# TRACKER.net
KiCad netlist of a schematic drawn in Altium Designer
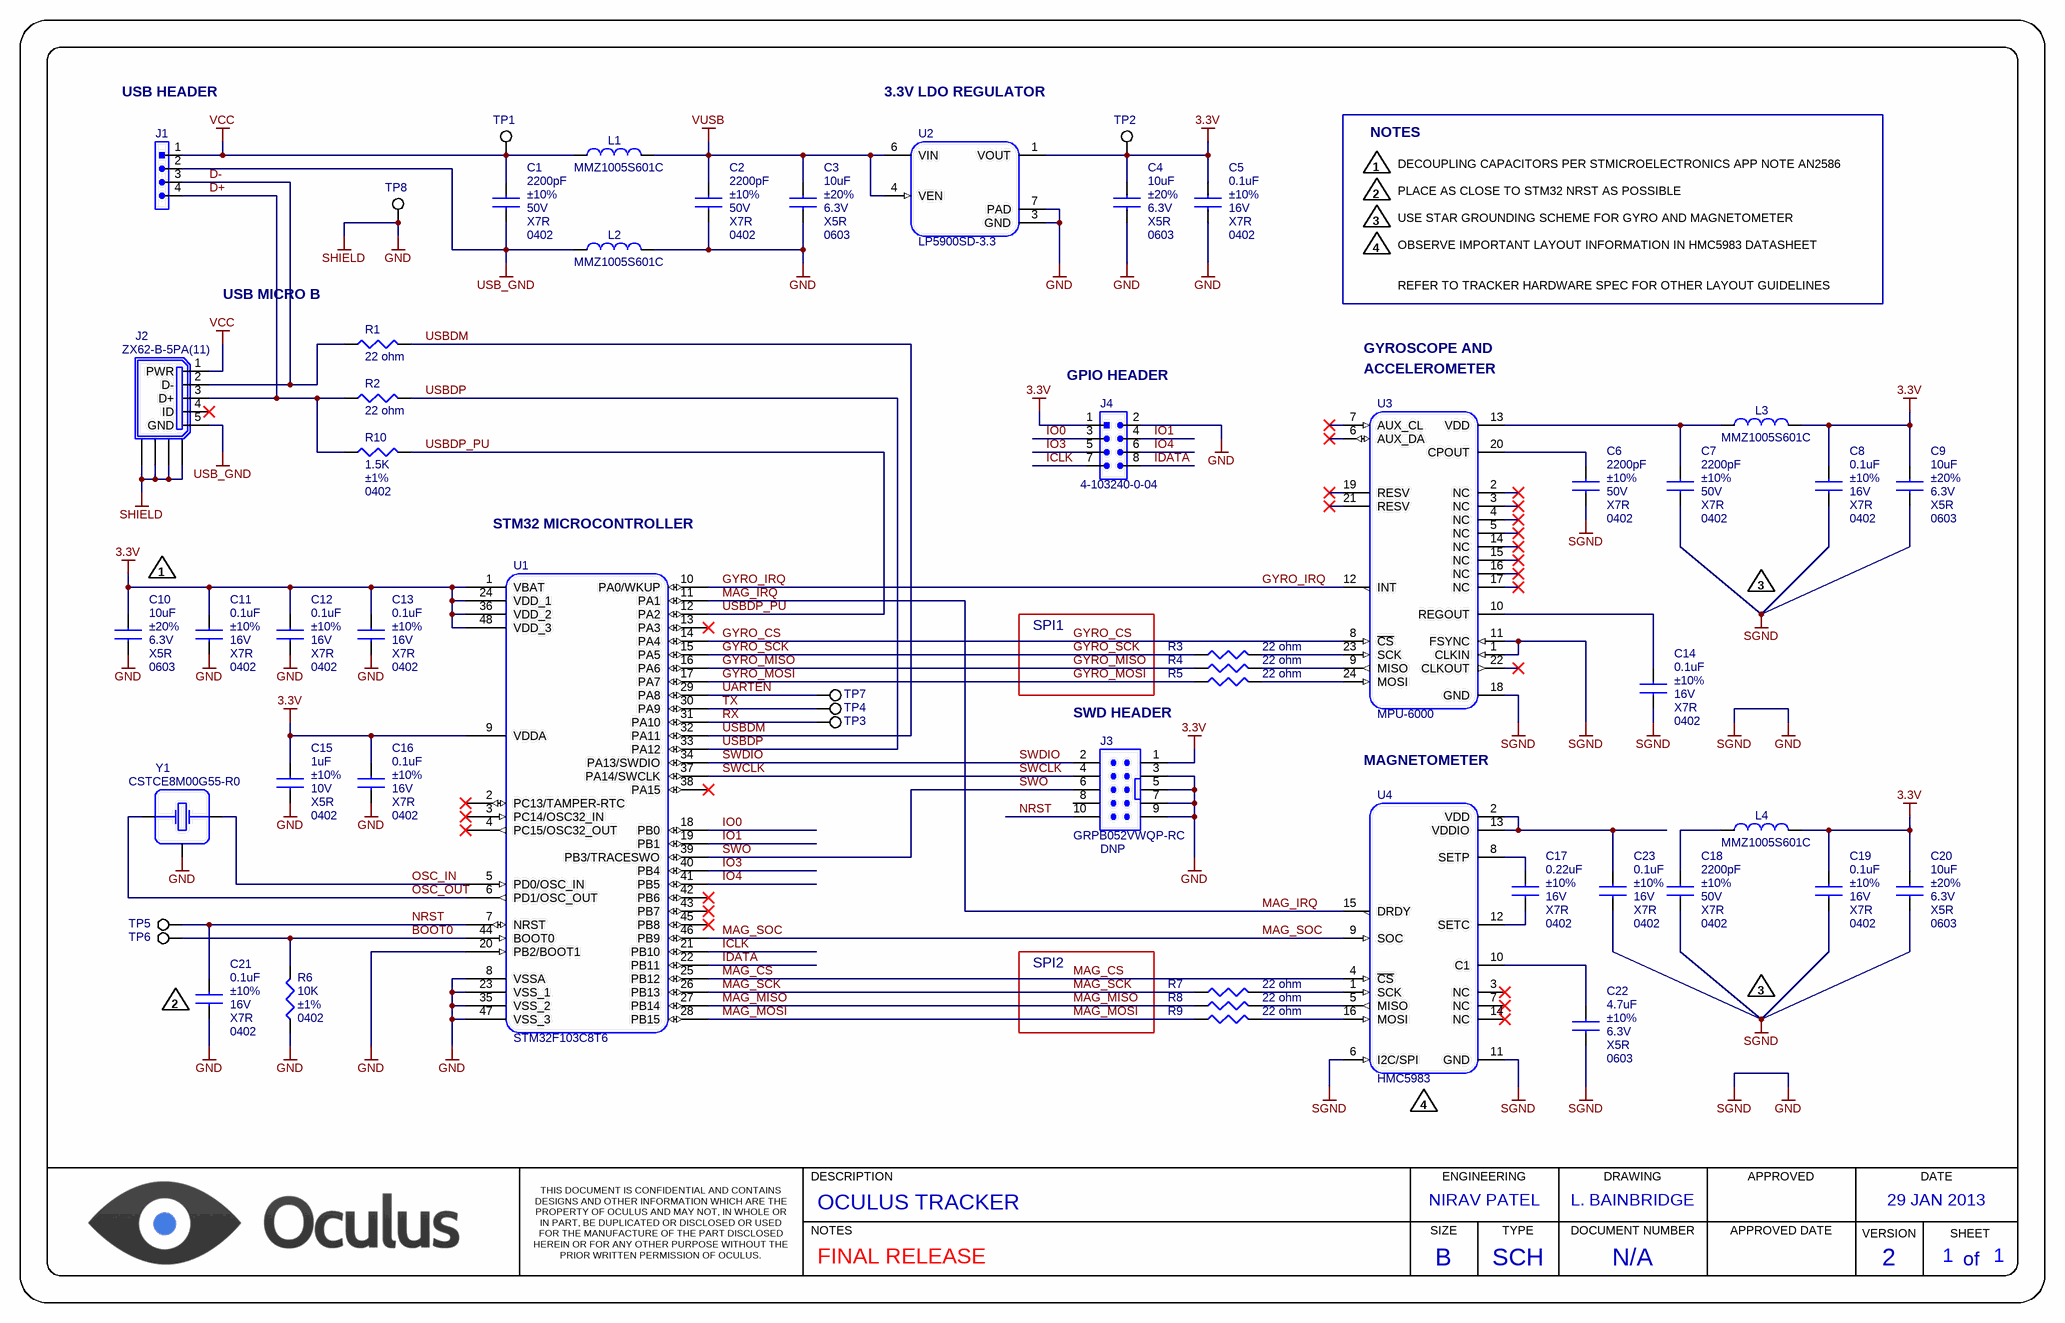
[diagram p0: TRACKER.SchDoc]

(export (version "E")
  (design (tool "Eeschema 10.0.6"))
  (components
    (comp (ref "C1")
      (value "2200pF")
      (footprint "CAP_CERAMIC_0402")
      (description "CAP, CERAMIC, 2200pF, ±10%, 50V, X7R, 0402")
      (fields
        (field (name "MANUFACTURER") "MURATA ELECTRONICS")
        (field (name "PART NUMBER") "GRM155R71H222KA01D")
        (field (name "TOLERANCE") "±10%")
        (field (name "VOLTAGE") "50V")
        (field (name "DIELECTRIC") "X7R")
        (field (name "PACKAGE") "0402")
      )
      (libsource (lib "TRACKER") (part "CAP, CERAMIC"))
    )
    (comp (ref "C2")
      (value "2200pF")
      (footprint "CAP_CERAMIC_0402")
      (description "CAP, CERAMIC, 2200pF, ±10%, 50V, X7R, 0402")
      (fields
        (field (name "MANUFACTURER") "MURATA ELECTRONICS")
        (field (name "PART NUMBER") "GRM155R71H222KA01D")
        (field (name "TOLERANCE") "±10%")
        (field (name "VOLTAGE") "50V")
        (field (name "DIELECTRIC") "X7R")
        (field (name "PACKAGE") "0402")
      )
      (libsource (lib "TRACKER") (part "CAP, CERAMIC"))
    )
    (comp (ref "C3")
      (value "10uF")
      (footprint "CAP_CERAMIC_0603")
      (description "CAP, CERAMIC, 10uF, ±20%, 6.3V, X5R, 0603")
      (fields
        (field (name "MANUFACTURER") "MURATA ELECTRONICS")
        (field (name "PART NUMBER") "GRM188R60J106ME47D")
        (field (name "TOLERANCE") "±20%")
        (field (name "VOLTAGE") "6.3V")
        (field (name "DIELECTRIC") "X5R")
        (field (name "PACKAGE") "0603")
      )
      (libsource (lib "TRACKER") (part "CAP, CERAMIC"))
    )
    (comp (ref "C4")
      (value "10uF")
      (footprint "CAP_CERAMIC_0603")
      (description "CAP, CERAMIC, 10uF, ±20%, 6.3V, X5R, 0603")
      (fields
        (field (name "MANUFACTURER") "MURATA ELECTRONICS")
        (field (name "PART NUMBER") "GRM188R60J106ME47D")
        (field (name "TOLERANCE") "±20%")
        (field (name "VOLTAGE") "6.3V")
        (field (name "DIELECTRIC") "X5R")
        (field (name "PACKAGE") "0603")
      )
      (libsource (lib "TRACKER") (part "CAP, CERAMIC"))
    )
    (comp (ref "C5")
      (value "0.1uF")
      (footprint "CAP_CERAMIC_0402")
      (description "CAP, CERAMIC, 0.1uF, ±10%, 16V, X7R, 0402")
      (fields
        (field (name "MANUFACTURER") "MURATA ELECTRONICS")
        (field (name "PART NUMBER") "GRM155R71C104KA88D")
        (field (name "TOLERANCE") "±10%")
        (field (name "VOLTAGE") "16V")
        (field (name "DIELECTRIC") "X7R")
        (field (name "PACKAGE") "0402")
      )
      (libsource (lib "TRACKER") (part "CAP, CERAMIC"))
    )
    (comp (ref "C6")
      (value "2200pF")
      (footprint "CAP_CERAMIC_0402")
      (description "CAP, CERAMIC, 2200pF, ±10%, 50V, X7R, 0402")
      (fields
        (field (name "MANUFACTURER") "MURATA ELECTRONICS")
        (field (name "PART NUMBER") "GRM155R71H222KA01D")
        (field (name "TOLERANCE") "±10%")
        (field (name "VOLTAGE") "50V")
        (field (name "DIELECTRIC") "X7R")
        (field (name "PACKAGE") "0402")
      )
      (libsource (lib "TRACKER") (part "CAP, CERAMIC"))
    )
    (comp (ref "C7")
      (value "2200pF")
      (footprint "CAP_CERAMIC_0402")
      (description "CAP, CERAMIC, 2200pF, ±10%, 50V, X7R, 0402")
      (fields
        (field (name "MANUFACTURER") "MURATA ELECTRONICS")
        (field (name "PART NUMBER") "GRM155R71H222KA01D")
        (field (name "TOLERANCE") "±10%")
        (field (name "VOLTAGE") "50V")
        (field (name "DIELECTRIC") "X7R")
        (field (name "PACKAGE") "0402")
      )
      (libsource (lib "TRACKER") (part "CAP, CERAMIC"))
    )
    (comp (ref "C8")
      (value "0.1uF")
      (footprint "CAP_CERAMIC_0402")
      (description "CAP, CERAMIC, 0.1uF, ±10%, 16V, X7R, 0402")
      (fields
        (field (name "MANUFACTURER") "MURATA ELECTRONICS")
        (field (name "PART NUMBER") "GRM155R71C104KA88D")
        (field (name "TOLERANCE") "±10%")
        (field (name "VOLTAGE") "16V")
        (field (name "DIELECTRIC") "X7R")
        (field (name "PACKAGE") "0402")
      )
      (libsource (lib "TRACKER") (part "CAP, CERAMIC"))
    )
    (comp (ref "C9")
      (value "10uF")
      (footprint "CAP_CERAMIC_0603")
      (description "CAP, CERAMIC, 10uF, ±20%, 6.3V, X5R, 0603")
      (fields
        (field (name "MANUFACTURER") "MURATA ELECTRONICS")
        (field (name "PART NUMBER") "GRM188R60J106ME47D")
        (field (name "TOLERANCE") "±20%")
        (field (name "VOLTAGE") "6.3V")
        (field (name "DIELECTRIC") "X5R")
        (field (name "PACKAGE") "0603")
      )
      (libsource (lib "TRACKER") (part "CAP, CERAMIC"))
    )
    (comp (ref "C10")
      (value "10uF")
      (footprint "CAP_CERAMIC_0603")
      (description "CAP, CERAMIC, 10uF, ±20%, 6.3V, X5R, 0603")
      (fields
        (field (name "MANUFACTURER") "MURATA ELECTRONICS")
        (field (name "PART NUMBER") "GRM188R60J106ME47D")
        (field (name "TOLERANCE") "±20%")
        (field (name "VOLTAGE") "6.3V")
        (field (name "DIELECTRIC") "X5R")
        (field (name "PACKAGE") "0603")
      )
      (libsource (lib "TRACKER") (part "CAP, CERAMIC"))
    )
    (comp (ref "C11")
      (value "0.1uF")
      (footprint "CAP_CERAMIC_0402")
      (description "CAP, CERAMIC, 0.1uF, ±10%, 16V, X7R, 0402")
      (fields
        (field (name "MANUFACTURER") "MURATA ELECTRONICS")
        (field (name "PART NUMBER") "GRM155R71C104KA88D")
        (field (name "TOLERANCE") "±10%")
        (field (name "VOLTAGE") "16V")
        (field (name "DIELECTRIC") "X7R")
        (field (name "PACKAGE") "0402")
      )
      (libsource (lib "TRACKER") (part "CAP, CERAMIC"))
    )
    (comp (ref "C12")
      (value "0.1uF")
      (footprint "CAP_CERAMIC_0402")
      (description "CAP, CERAMIC, 0.1uF, ±10%, 16V, X7R, 0402")
      (fields
        (field (name "MANUFACTURER") "MURATA ELECTRONICS")
        (field (name "PART NUMBER") "GRM155R71C104KA88D")
        (field (name "TOLERANCE") "±10%")
        (field (name "VOLTAGE") "16V")
        (field (name "DIELECTRIC") "X7R")
        (field (name "PACKAGE") "0402")
      )
      (libsource (lib "TRACKER") (part "CAP, CERAMIC"))
    )
    (comp (ref "C13")
      (value "0.1uF")
      (footprint "CAP_CERAMIC_0402")
      (description "CAP, CERAMIC, 0.1uF, ±10%, 16V, X7R, 0402")
      (fields
        (field (name "MANUFACTURER") "MURATA ELECTRONICS")
        (field (name "PART NUMBER") "GRM155R71C104KA88D")
        (field (name "TOLERANCE") "±10%")
        (field (name "VOLTAGE") "16V")
        (field (name "DIELECTRIC") "X7R")
        (field (name "PACKAGE") "0402")
      )
      (libsource (lib "TRACKER") (part "CAP, CERAMIC"))
    )
    (comp (ref "C14")
      (value "0.1uF")
      (footprint "CAP_CERAMIC_0402")
      (description "CAP, CERAMIC, 0.1uF, ±10%, 16V, X7R, 0402")
      (fields
        (field (name "MANUFACTURER") "MURATA ELECTRONICS")
        (field (name "PART NUMBER") "GRM155R71C104KA88D")
        (field (name "TOLERANCE") "±10%")
        (field (name "VOLTAGE") "16V")
        (field (name "DIELECTRIC") "X7R")
        (field (name "PACKAGE") "0402")
      )
      (libsource (lib "TRACKER") (part "CAP, CERAMIC"))
    )
    (comp (ref "C15")
      (value "1uF")
      (footprint "CAP_CERAMIC_0402")
      (description "CAP, CERAMIC, 1uF, ±10%, 10V, X5R, 0402")
      (fields
        (field (name "MANUFACTURER") "MURATA ELECTRONICS")
        (field (name "PART NUMBER") "GRM155R61A105KE15D")
        (field (name "TOLERANCE") "±10%")
        (field (name "VOLTAGE") "10V")
        (field (name "DIELECTRIC") "X5R")
        (field (name "PACKAGE") "0402")
      )
      (libsource (lib "TRACKER") (part "CAP, CERAMIC"))
    )
    (comp (ref "C16")
      (value "0.1uF")
      (footprint "CAP_CERAMIC_0402")
      (description "CAP, CERAMIC, 0.1uF, ±10%, 16V, X7R, 0402")
      (fields
        (field (name "MANUFACTURER") "MURATA ELECTRONICS")
        (field (name "PART NUMBER") "GRM155R71C104KA88D")
        (field (name "TOLERANCE") "±10%")
        (field (name "VOLTAGE") "16V")
        (field (name "DIELECTRIC") "X7R")
        (field (name "PACKAGE") "0402")
      )
      (libsource (lib "TRACKER") (part "CAP, CERAMIC"))
    )
    (comp (ref "C17")
      (value "0.22uF")
      (footprint "CAP_CERAMIC_0402")
      (description "CAP, CERAMIC, 0.22uF, ±10%, 16V, X7R, 0402")
      (fields
        (field (name "MANUFACTURER") "MURATA ELECTRONICS")
        (field (name "PART NUMBER") "GRM155R71C224KA12D")
        (field (name "TOLERANCE") "±10%")
        (field (name "VOLTAGE") "16V")
        (field (name "DIELECTRIC") "X7R")
        (field (name "PACKAGE") "0402")
      )
      (libsource (lib "TRACKER") (part "CAP, CERAMIC"))
    )
    (comp (ref "C18")
      (value "2200pF")
      (footprint "CAP_CERAMIC_0402")
      (description "CAP, CERAMIC, 2200pF, ±10%, 50V, X7R, 0402")
      (fields
        (field (name "MANUFACTURER") "MURATA ELECTRONICS")
        (field (name "PART NUMBER") "GRM155R71H222KA01D")
        (field (name "TOLERANCE") "±10%")
        (field (name "VOLTAGE") "50V")
        (field (name "DIELECTRIC") "X7R")
        (field (name "PACKAGE") "0402")
      )
      (libsource (lib "TRACKER") (part "CAP, CERAMIC"))
    )
    (comp (ref "C19")
      (value "0.1uF")
      (footprint "CAP_CERAMIC_0402")
      (description "CAP, CERAMIC, 0.1uF, ±10%, 16V, X7R, 0402")
      (fields
        (field (name "MANUFACTURER") "MURATA ELECTRONICS")
        (field (name "PART NUMBER") "GRM155R71C104KA88D")
        (field (name "TOLERANCE") "±10%")
        (field (name "VOLTAGE") "16V")
        (field (name "DIELECTRIC") "X7R")
        (field (name "PACKAGE") "0402")
      )
      (libsource (lib "TRACKER") (part "CAP, CERAMIC"))
    )
    (comp (ref "C20")
      (value "10uF")
      (footprint "CAP_CERAMIC_0603")
      (description "CAP, CERAMIC, 10uF, ±20%, 6.3V, X5R, 0603")
      (fields
        (field (name "MANUFACTURER") "MURATA ELECTRONICS")
        (field (name "PART NUMBER") "GRM188R60J106ME47D")
        (field (name "TOLERANCE") "±20%")
        (field (name "VOLTAGE") "6.3V")
        (field (name "DIELECTRIC") "X5R")
        (field (name "PACKAGE") "0603")
      )
      (libsource (lib "TRACKER") (part "CAP, CERAMIC"))
    )
    (comp (ref "C21")
      (value "0.1uF")
      (footprint "CAP_CERAMIC_0402")
      (description "CAP, CERAMIC, 0.1uF, ±10%, 16V, X7R, 0402")
      (fields
        (field (name "MANUFACTURER") "MURATA ELECTRONICS")
        (field (name "PART NUMBER") "GRM155R71C104KA88D")
        (field (name "TOLERANCE") "±10%")
        (field (name "VOLTAGE") "16V")
        (field (name "DIELECTRIC") "X7R")
        (field (name "PACKAGE") "0402")
      )
      (libsource (lib "TRACKER") (part "CAP, CERAMIC"))
    )
    (comp (ref "C22")
      (value "4.7uF")
      (footprint "CAP_CERAMIC_0603")
      (description "CAP, CERAMIC, 4.7uF, ±10%, 6.3V, X5R, 0603")
      (fields
        (field (name "MANUFACTURER") "MURATA ELECTRONICS")
        (field (name "PART NUMBER") "GRM188R60J475KE19D")
        (field (name "TOLERANCE") "±10%")
        (field (name "VOLTAGE") "6.3V")
        (field (name "DIELECTRIC") "X5R")
        (field (name "PACKAGE") "0603")
      )
      (libsource (lib "TRACKER") (part "CAP, CERAMIC"))
    )
    (comp (ref "C23")
      (value "0.1uF")
      (footprint "CAP_CERAMIC_0402")
      (description "CAP, CERAMIC, 0.1uF, ±10%, 16V, X7R, 0402")
      (fields
        (field (name "MANUFACTURER") "MURATA ELECTRONICS")
        (field (name "PART NUMBER") "GRM155R71C104KA88D")
        (field (name "TOLERANCE") "±10%")
        (field (name "VOLTAGE") "16V")
        (field (name "DIELECTRIC") "X7R")
        (field (name "PACKAGE") "0402")
      )
      (libsource (lib "TRACKER") (part "CAP, CERAMIC"))
    )
    (comp (ref "J1")
      (value "USB_HEADER")
      (footprint "USB_HEADER")
      (description "CONNECTOR, HEADER, 4 POS")
      (fields (field (name "MANUFACTURER") "TBD"))
      (libsource (lib "TRACKER") (part "USB_HEADER"))
    )
    (comp (ref "J2")
      (value "ZX62-B-5PA(11)")
      (footprint "ZX62-B-5PA(11)")
      (description "CONNECTOR, USB MICRO B, R/A, SMD")
      (fields (field (name "MANUFACTURER") "HIROSE"))
      (libsource (lib "TRACKER") (part "ZX62-B-5PA(11)"))
    )
    (comp (ref "J3")
      (value "GRPB052VWQP-RC")
      (footprint "GRPB052VWQP-RC")
      (description "CONNECTOR, 10 POS, ARM CORTEX SWD HEADER")
      (fields (field (name "MANUFACTURER") "SULLINS CONNECTOR") (field (name "DNP") "DNP"))
      (libsource (lib "TRACKER") (part "GRPB052VWQP-RC"))
    )
    (comp (ref "J4")
      (value "4-103240-0-04")
      (footprint "4-103240-0-04")
      (description "CONNECTOR, HEADER, 2X4, 0.1\" PITCH")
      (fields (field (name "MANUFACTURER") "TE CONNECTIVITY"))
      (libsource (lib "TRACKER") (part "4-103240-0-04"))
    )
    (comp (ref "L1")
      (value "MMZ1005S601C")
      (footprint "INDUCTOR_0402")
      (description "FERRITE CHIP BEAD, 600 OHM @ 100MHz, 300mA, 0402")
      (fields (field (name "MANUFACTURER") "TDK CORPORATION"))
      (libsource (lib "TRACKER") (part "INDUCTOR"))
    )
    (comp (ref "L2")
      (value "MMZ1005S601C")
      (footprint "INDUCTOR_0402")
      (description "FERRITE CHIP BEAD, 600 OHM @ 100MHz, 300mA, 0402")
      (fields (field (name "MANUFACTURER") "TDK CORPORATION"))
      (libsource (lib "TRACKER") (part "INDUCTOR"))
    )
    (comp (ref "L3")
      (value "MMZ1005S601C")
      (footprint "INDUCTOR_0402")
      (description "FERRITE CHIP BEAD, 600 OHM @ 100MHz, 300mA, 0402")
      (fields (field (name "MANUFACTURER") "TDK CORPORATION"))
      (libsource (lib "TRACKER") (part "INDUCTOR"))
    )
    (comp (ref "L4")
      (value "MMZ1005S601C")
      (footprint "INDUCTOR_0402")
      (description "FERRITE CHIP BEAD, 600 OHM @ 100MHz, 300mA, 0402")
      (fields (field (name "MANUFACTURER") "TDK CORPORATION"))
      (libsource (lib "TRACKER") (part "INDUCTOR"))
    )
    (comp (ref "R1")
      (value "22 ohm")
      (footprint "RESISTOR_0402")
      (description "RES, 22 OHM, 1/10W, ±1%, 0402")
      (fields (field (name "MANUFACTURER") "PANASONIC") (field (name "PART NUMBER") "ERJ-2RKF22R0X"))
      (libsource (lib "TRACKER") (part "RESISTOR"))
    )
    (comp (ref "R2")
      (value "22 ohm")
      (footprint "RESISTOR_0402")
      (description "RES, 22 OHM, 1/10W, ±1%, 0402")
      (fields (field (name "MANUFACTURER") "PANASONIC") (field (name "PART NUMBER") "ERJ-2RKF22R0X"))
      (libsource (lib "TRACKER") (part "RESISTOR"))
    )
    (comp (ref "R3")
      (value "22 ohm")
      (footprint "RESISTOR_0402")
      (description "RES, 22 OHM, 1/10W, ±1%, 0402")
      (fields (field (name "MANUFACTURER") "PANASONIC") (field (name "PART NUMBER") "ERJ-2RKF22R0X"))
      (libsource (lib "TRACKER") (part "RESISTOR"))
    )
    (comp (ref "R4")
      (value "22 ohm")
      (footprint "RESISTOR_0402")
      (description "RES, 22 OHM, 1/10W, ±1%, 0402")
      (fields (field (name "MANUFACTURER") "PANASONIC") (field (name "PART NUMBER") "ERJ-2RKF22R0X"))
      (libsource (lib "TRACKER") (part "RESISTOR"))
    )
    (comp (ref "R5")
      (value "22 ohm")
      (footprint "RESISTOR_0402")
      (description "RES, 22 OHM, 1/10W, ±1%, 0402")
      (fields (field (name "MANUFACTURER") "PANASONIC") (field (name "PART NUMBER") "ERJ-2RKF22R0X"))
      (libsource (lib "TRACKER") (part "RESISTOR"))
    )
    (comp (ref "R6")
      (value "10K")
      (footprint "RESISTOR_0402")
      (description "RES, 10K OHM, 1/10W, ±1%, 0402")
      (fields
        (field (name "MANUFACTURER") "PANASONIC")
        (field (name "PART NUMBER") "ERJ-2RKF1002X")
        (field (name "PACKAGE") "0402")
        (field (name "TOLERANCE") "±1%")
      )
      (libsource (lib "TRACKER") (part "RESISTOR"))
    )
    (comp (ref "R7")
      (value "22 ohm")
      (footprint "RESISTOR_0402")
      (description "RES, 22 OHM, 1/10W, ±1%, 0402")
      (fields (field (name "MANUFACTURER") "PANASONIC") (field (name "PART NUMBER") "ERJ-2RKF22R0X"))
      (libsource (lib "TRACKER") (part "RESISTOR"))
    )
    (comp (ref "R8")
      (value "22 ohm")
      (footprint "RESISTOR_0402")
      (description "RES, 22 OHM, 1/10W, ±1%, 0402")
      (fields (field (name "MANUFACTURER") "PANASONIC") (field (name "PART NUMBER") "ERJ-2RKF22R0X"))
      (libsource (lib "TRACKER") (part "RESISTOR"))
    )
    (comp (ref "R9")
      (value "22 ohm")
      (footprint "RESISTOR_0402")
      (description "RES, 22 OHM, 1/10W, ±1%, 0402")
      (fields (field (name "MANUFACTURER") "PANASONIC") (field (name "PART NUMBER") "ERJ-2RKF22R0X"))
      (libsource (lib "TRACKER") (part "RESISTOR"))
    )
    (comp (ref "R10")
      (value "1.5K")
      (footprint "RESISTOR_0402")
      (description "RES, 1.5K OHM, 1/10W, ±1%, 0402")
      (fields
        (field (name "MANUFACTURER") "PANASONIC")
        (field (name "PART NUMBER") "ERJ-2RKF1501X")
        (field (name "PACKAGE") "0402")
        (field (name "TOLERANCE") "±1%")
      )
      (libsource (lib "TRACKER") (part "RESISTOR"))
    )
    (comp (ref "TP1")
      (value "TEST POINT")
      (footprint "TEST_POINT_PAD")
      (libsource (lib "TRACKER") (part "TEST_POINT"))
    )
    (comp (ref "TP2")
      (value "TEST POINT")
      (footprint "TEST_POINT_PAD")
      (libsource (lib "TRACKER") (part "TEST_POINT"))
    )
    (comp (ref "TP3")
      (value "TEST POINT")
      (footprint "TEST_POINT_PAD")
      (libsource (lib "TRACKER") (part "TEST_POINT"))
    )
    (comp (ref "TP4")
      (value "TEST POINT")
      (footprint "TEST_POINT_PAD")
      (libsource (lib "TRACKER") (part "TEST_POINT"))
    )
    (comp (ref "TP5")
      (value "TEST POINT")
      (footprint "TEST_POINT_PAD")
      (libsource (lib "TRACKER") (part "TEST_POINT"))
    )
    (comp (ref "TP6")
      (value "TEST POINT")
      (footprint "TEST_POINT_PAD")
      (libsource (lib "TRACKER") (part "TEST_POINT"))
    )
    (comp (ref "TP7")
      (value "TEST POINT")
      (footprint "TEST_POINT_PAD")
      (libsource (lib "TRACKER") (part "TEST_POINT"))
    )
    (comp (ref "TP8")
      (value "TEST POINT")
      (footprint "TEST_POINT_PAD")
      (libsource (lib "TRACKER") (part "TEST_POINT"))
    )
    (comp (ref "U1")
      (value "STM32F103C8T6")
      (footprint "LQFP48")
      (description "IC, STM32 MICROCONTROLLER, ARM CORTEX M3")
      (fields (field (name "MANUFACTURER") "ST MICROELECTRONICS"))
      (libsource (lib "TRACKER") (part "STM32F103C8T6"))
    )
    (comp (ref "U2")
      (value "LP5900SD-3.3")
      (footprint "LLP-6")
      (description "IC, LINEAR REGULATOR, 3.3V, 150MA, ULTRA LOW NOISE")
      (fields
        (field (name "MANUFACTURER") "NATIONAL SEMICONDUCTOR")
        (field (name "PART NUMBER") "LP5900SD-3.3/NOPB")
      )
      (libsource (lib "TRACKER") (part "LP5900SD-3.3"))
    )
    (comp (ref "U3")
      (value "MPU-6000")
      (footprint "QFN-24")
      (description "IC, MEMS 3 AXIS GYROSCOPE AND 3 AXIS ACCELEROMETER")
      (fields (field (name "MANUFACTURER") "INVENSENSE"))
      (libsource (lib "TRACKER") (part "MPU-6000"))
    )
    (comp (ref "U4")
      (value "HMC5983")
      (footprint "LPCC-16")
      (description "IC, MEMS 3 AXIS MAGNETOMETER")
      (fields (field (name "MANUFACTURER") "HONEYWELL") (field (name "PART NUMBER") "HMC5983-TR"))
      (libsource (lib "TRACKER") (part "HMC5983"))
    )
    (comp (ref "Y1")
      (value "CSTCE8M00G55-R0")
      (footprint "CSTCE")
      (description "CERAMIC RESONATOR, 8MHz, +/-0.2%, 33pF, SMD")
      (fields (field (name "MANUFACTURER") "MURATA ELECTRONICS"))
      (libsource (lib "TRACKER") (part "CSTCE8M00G55-R0"))
    )
  )
  (nets
    (net (code "1") (name "/BOOT0") (class "Default")
      (node (ref "R6") (pin "2") (pinfunction "2_2") (pintype "passive"))
      (node (ref "TP6") (pin "1") (pinfunction "1_1") (pintype "passive"))
      (node (ref "U1") (pin "44") (pinfunction "BOOT0_44") (pintype "input"))
    )
    (net (code "2") (name "/D+") (class "Default")
      (node (ref "J1") (pin "4") (pintype "passive"))
      (node (ref "J2") (pin "3") (pinfunction "D+_3") (pintype "tri_state"))
      (node (ref "R10") (pin "1") (pinfunction "1_1") (pintype "passive"))
      (node (ref "R2") (pin "1") (pinfunction "1_1") (pintype "passive"))
    )
    (net (code "3") (name "/D-") (class "Default")
      (node (ref "J1") (pin "3") (pintype "passive"))
      (node (ref "J2") (pin "2") (pinfunction "D-_2") (pintype "tri_state"))
      (node (ref "R1") (pin "1") (pinfunction "1_1") (pintype "passive"))
    )
    (net (code "4") (name "/GYRO_CS") (class "Default")
      (node (ref "U1") (pin "14") (pinfunction "PA4_14") (pintype "bidirectional"))
      (node (ref "U3") (pin "8") (pinfunction "~{CS}_8") (pintype "input"))
    )
    (net (code "5") (name "/GYRO_IRQ") (class "Default")
      (node (ref "U1") (pin "10") (pinfunction "PA0/WKUP_10") (pintype "bidirectional"))
      (node (ref "U3") (pin "12") (pinfunction "INT_12") (pintype "passive"))
    )
    (net (code "6") (name "/GYRO_MISO") (class "Default")
      (node (ref "R4") (pin "1") (pinfunction "1_1") (pintype "passive"))
      (node (ref "U1") (pin "16") (pinfunction "PA6_16") (pintype "bidirectional"))
    )
    (net (code "7") (name "/GYRO_MOSI") (class "Default")
      (node (ref "R5") (pin "1") (pinfunction "1_1") (pintype "passive"))
      (node (ref "U1") (pin "17") (pinfunction "PA7_17") (pintype "bidirectional"))
    )
    (net (code "8") (name "/GYRO_SCK") (class "Default")
      (node (ref "R3") (pin "1") (pinfunction "1_1") (pintype "passive"))
      (node (ref "U1") (pin "15") (pinfunction "PA5_15") (pintype "bidirectional"))
    )
    (net (code "9") (name "/ICLK") (class "Default")
      (node (ref "J4") (pin "7") (pintype "passive"))
      (node (ref "U1") (pin "21") (pinfunction "PB10_21") (pintype "bidirectional"))
    )
    (net (code "10") (name "/IDATA") (class "Default")
      (node (ref "J4") (pin "8") (pintype "passive"))
      (node (ref "U1") (pin "22") (pinfunction "PB11_22") (pintype "bidirectional"))
    )
    (net (code "11") (name "/IO0") (class "Default")
      (node (ref "J4") (pin "3") (pintype "passive"))
      (node (ref "U1") (pin "18") (pinfunction "PB0_18") (pintype "bidirectional"))
    )
    (net (code "12") (name "/IO1") (class "Default")
      (node (ref "J4") (pin "4") (pintype "passive"))
      (node (ref "U1") (pin "19") (pinfunction "PB1_19") (pintype "bidirectional"))
    )
    (net (code "13") (name "/IO3") (class "Default")
      (node (ref "J4") (pin "5") (pintype "passive"))
      (node (ref "U1") (pin "40") (pinfunction "PB4_40") (pintype "bidirectional"))
    )
    (net (code "14") (name "/IO4") (class "Default")
      (node (ref "J4") (pin "6") (pintype "passive"))
      (node (ref "U1") (pin "41") (pinfunction "PB5_41") (pintype "bidirectional"))
    )
    (net (code "15") (name "/MAG_CS") (class "Default")
      (node (ref "U1") (pin "25") (pinfunction "PB12_25") (pintype "bidirectional"))
      (node (ref "U4") (pin "4") (pinfunction "~{CS}_4") (pintype "input"))
    )
    (net (code "16") (name "/MAG_IRQ") (class "Default")
      (node (ref "U1") (pin "11") (pinfunction "PA1_11") (pintype "bidirectional"))
      (node (ref "U4") (pin "15") (pinfunction "DRDY_15") (pintype "passive"))
    )
    (net (code "17") (name "/MAG_MISO") (class "Default")
      (node (ref "R8") (pin "1") (pinfunction "1_1") (pintype "passive"))
      (node (ref "U1") (pin "27") (pinfunction "PB14_27") (pintype "bidirectional"))
    )
    (net (code "18") (name "/MAG_MOSI") (class "Default")
      (node (ref "R9") (pin "1") (pinfunction "1_1") (pintype "passive"))
      (node (ref "U1") (pin "28") (pinfunction "PB15_28") (pintype "bidirectional"))
    )
    (net (code "19") (name "/MAG_SCK") (class "Default")
      (node (ref "R7") (pin "1") (pinfunction "1_1") (pintype "passive"))
      (node (ref "U1") (pin "26") (pinfunction "PB13_26") (pintype "bidirectional"))
    )
    (net (code "20") (name "/MAG_SOC") (class "Default")
      (node (ref "U1") (pin "46") (pinfunction "PB9_46") (pintype "bidirectional"))
      (node (ref "U4") (pin "9") (pinfunction "SOC_9") (pintype "input"))
    )
    (net (code "21") (name "/NRST") (class "Default")
      (node (ref "C21") (pin "1") (pinfunction "1_1") (pintype "passive"))
      (node (ref "J3") (pin "10") (pintype "passive"))
      (node (ref "TP5") (pin "1") (pinfunction "1_1") (pintype "passive"))
      (node (ref "U1") (pin "7") (pinfunction "NRST_7") (pintype "bidirectional"))
    )
    (net (code "22") (name "/OSC_IN") (class "Default")
      (node (ref "U1") (pin "5") (pinfunction "PD0/OSC_IN_5") (pintype "input"))
      (node (ref "Y1") (pin "3") (pinfunction "3_3") (pintype "passive"))
    )
    (net (code "23") (name "/OSC_OUT") (class "Default")
      (node (ref "U1") (pin "6") (pinfunction "PD1/OSC_OUT_6") (pintype "output"))
      (node (ref "Y1") (pin "1") (pinfunction "1_1") (pintype "passive"))
    )
    (net (code "24") (name "/RX") (class "Default")
      (node (ref "TP3") (pin "1") (pinfunction "1_1") (pintype "passive"))
      (node (ref "U1") (pin "31") (pinfunction "PA10_31") (pintype "bidirectional"))
    )
    (net (code "25") (name "/SWCLK") (class "Default")
      (node (ref "J3") (pin "4") (pintype "passive"))
      (node (ref "U1") (pin "37") (pinfunction "PA14/SWCLK_37") (pintype "bidirectional"))
    )
    (net (code "26") (name "/SWDIO") (class "Default")
      (node (ref "J3") (pin "2") (pintype "passive"))
      (node (ref "U1") (pin "34") (pinfunction "PA13/SWDIO_34") (pintype "bidirectional"))
    )
    (net (code "27") (name "/SWO") (class "Default")
      (node (ref "J3") (pin "6") (pintype "passive"))
      (node (ref "U1") (pin "39") (pinfunction "PB3/TRACESWO_39") (pintype "bidirectional"))
    )
    (net (code "28") (name "/TX") (class "Default")
      (node (ref "TP4") (pin "1") (pinfunction "1_1") (pintype "passive"))
      (node (ref "U1") (pin "30") (pinfunction "PA9_30") (pintype "bidirectional"))
    )
    (net (code "29") (name "/UARTEN") (class "Default")
      (node (ref "TP7") (pin "1") (pinfunction "1_1") (pintype "passive"))
      (node (ref "U1") (pin "29") (pinfunction "PA8_29") (pintype "bidirectional"))
    )
    (net (code "30") (name "/USBDM") (class "Default")
      (node (ref "R1") (pin "2") (pinfunction "2_2") (pintype "passive"))
      (node (ref "U1") (pin "32") (pinfunction "PA11_32") (pintype "bidirectional"))
    )
    (net (code "31") (name "/USBDP") (class "Default")
      (node (ref "R2") (pin "2") (pinfunction "2_2") (pintype "passive"))
      (node (ref "U1") (pin "33") (pinfunction "PA12_33") (pintype "bidirectional"))
    )
    (net (code "32") (name "/USBDP_PU") (class "Default")
      (node (ref "R10") (pin "2") (pinfunction "2_2") (pintype "passive"))
      (node (ref "U1") (pin "12") (pinfunction "PA2_12") (pintype "bidirectional"))
    )
    (net (code "33") (name "3.3V") (class "Default")
      (node (ref "C10") (pin "1") (pinfunction "1_1") (pintype "passive"))
      (node (ref "C11") (pin "1") (pinfunction "1_1") (pintype "passive"))
      (node (ref "C12") (pin "1") (pinfunction "1_1") (pintype "passive"))
      (node (ref "C13") (pin "1") (pinfunction "1_1") (pintype "passive"))
      (node (ref "C15") (pin "1") (pinfunction "1_1") (pintype "passive"))
      (node (ref "C16") (pin "1") (pinfunction "1_1") (pintype "passive"))
      (node (ref "C19") (pin "1") (pinfunction "1_1") (pintype "passive"))
      (node (ref "C20") (pin "1") (pinfunction "1_1") (pintype "passive"))
      (node (ref "C4") (pin "1") (pinfunction "1_1") (pintype "passive"))
      (node (ref "C5") (pin "1") (pinfunction "1_1") (pintype "passive"))
      (node (ref "C8") (pin "1") (pinfunction "1_1") (pintype "passive"))
      (node (ref "C9") (pin "1") (pinfunction "1_1") (pintype "passive"))
      (node (ref "J3") (pin "1") (pintype "passive"))
      (node (ref "J4") (pin "1") (pintype "passive"))
      (node (ref "L3") (pin "2") (pinfunction "2_2") (pintype "passive"))
      (node (ref "L4") (pin "2") (pinfunction "2_2") (pintype "passive"))
      (node (ref "TP2") (pin "1") (pinfunction "1_1") (pintype "passive"))
      (node (ref "U1") (pin "1") (pinfunction "VBAT_1") (pintype "power_in"))
      (node (ref "U1") (pin "24") (pinfunction "VDD_1_24") (pintype "power_in"))
      (node (ref "U1") (pin "36") (pinfunction "VDD_2_36") (pintype "power_in"))
      (node (ref "U1") (pin "48") (pinfunction "VDD_3_48") (pintype "power_in"))
      (node (ref "U1") (pin "9") (pinfunction "VDDA_9") (pintype "power_in"))
      (node (ref "U2") (pin "1") (pinfunction "VOUT_1") (pintype "power_in"))
    )
    (net (code "34") (name "GND") (class "Default")
      (node (ref "C10") (pin "2") (pinfunction "2_2") (pintype "passive"))
      (node (ref "C11") (pin "2") (pinfunction "2_2") (pintype "passive"))
      (node (ref "C12") (pin "2") (pinfunction "2_2") (pintype "passive"))
      (node (ref "C13") (pin "2") (pinfunction "2_2") (pintype "passive"))
      (node (ref "C14") (pin "2") (pinfunction "2_2") (pintype "passive"))
      (node (ref "C15") (pin "2") (pinfunction "2_2") (pintype "passive"))
      (node (ref "C16") (pin "2") (pinfunction "2_2") (pintype "passive"))
      (node (ref "C18") (pin "2") (pinfunction "2_2") (pintype "passive"))
      (node (ref "C19") (pin "2") (pinfunction "2_2") (pintype "passive"))
      (node (ref "C2") (pin "2") (pinfunction "2_2") (pintype "passive"))
      (node (ref "C20") (pin "2") (pinfunction "2_2") (pintype "passive"))
      (node (ref "C21") (pin "2") (pinfunction "2_2") (pintype "passive"))
      (node (ref "C22") (pin "2") (pinfunction "2_2") (pintype "passive"))
      (node (ref "C23") (pin "2") (pinfunction "2_2") (pintype "passive"))
      (node (ref "C3") (pin "2") (pinfunction "2_2") (pintype "passive"))
      (node (ref "C4") (pin "2") (pinfunction "2_2") (pintype "passive"))
      (node (ref "C5") (pin "2") (pinfunction "2_2") (pintype "passive"))
      (node (ref "C6") (pin "2") (pinfunction "2_2") (pintype "passive"))
      (node (ref "C7") (pin "2") (pinfunction "2_2") (pintype "passive"))
      (node (ref "C8") (pin "2") (pinfunction "2_2") (pintype "passive"))
      (node (ref "C9") (pin "2") (pinfunction "2_2") (pintype "passive"))
      (node (ref "J2") (pin "6") (pinfunction "SHIELD_6") (pintype "passive"))
      (node (ref "J2") (pin "7") (pinfunction "SHIELD_7") (pintype "passive"))
      (node (ref "J2") (pin "8") (pinfunction "SHIELD_8") (pintype "passive"))
      (node (ref "J2") (pin "9") (pinfunction "SHIELD_9") (pintype "passive"))
      (node (ref "J3") (pin "3") (pintype "passive"))
      (node (ref "J3") (pin "5") (pintype "passive"))
      (node (ref "J3") (pin "7") (pintype "passive"))
      (node (ref "J3") (pin "9") (pintype "passive"))
      (node (ref "J4") (pin "2") (pintype "passive"))
      (node (ref "L2") (pin "2") (pinfunction "2_2") (pintype "passive"))
      (node (ref "R6") (pin "1") (pinfunction "1_1") (pintype "passive"))
      (node (ref "TP8") (pin "1") (pinfunction "1_1") (pintype "passive"))
      (node (ref "U1") (pin "20") (pinfunction "PB2/BOOT1_20") (pintype "input"))
      (node (ref "U1") (pin "23") (pinfunction "VSS_1_23") (pintype "power_in"))
      (node (ref "U1") (pin "35") (pinfunction "VSS_2_35") (pintype "power_in"))
      (node (ref "U1") (pin "47") (pinfunction "VSS_3_47") (pintype "power_in"))
      (node (ref "U1") (pin "8") (pinfunction "VSSA_8") (pintype "power_in"))
      (node (ref "U2") (pin "3") (pinfunction "GND_3") (pintype "power_in"))
      (node (ref "U2") (pin "7") (pinfunction "PAD_7") (pintype "power_in"))
      (node (ref "U3") (pin "1") (pinfunction "CLKIN_1") (pintype "input"))
      (node (ref "U3") (pin "11") (pinfunction "FSYNC_11") (pintype "input"))
      (node (ref "U3") (pin "18") (pinfunction "GND_18") (pintype "power_in"))
      (node (ref "U4") (pin "11") (pinfunction "GND_11") (pintype "power_in"))
      (node (ref "U4") (pin "6") (pinfunction "I2C/SPI_6") (pintype "input"))
      (node (ref "Y1") (pin "2") (pinfunction "GND_2") (pintype "power_in"))
    )
    (net (code "35") (name "Net-(C18-Pad1)") (class "Default")
      (node (ref "C18") (pin "1") (pinfunction "1_1") (pintype "passive"))
      (node (ref "L4") (pin "1") (pinfunction "1_1") (pintype "passive"))
    )
    (net (code "36") (name "Net-(U3-CPOUT)") (class "Default")
      (node (ref "C6") (pin "1") (pinfunction "1_1") (pintype "passive"))
      (node (ref "U3") (pin "20") (pinfunction "CPOUT_20") (pintype "passive"))
    )
    (net (code "37") (name "Net-(U3-MISO)") (class "Default")
      (node (ref "R4") (pin "2") (pinfunction "2_2") (pintype "passive"))
      (node (ref "U3") (pin "9") (pinfunction "MISO_9") (pintype "output"))
    )
    (net (code "38") (name "Net-(U3-MOSI)") (class "Default")
      (node (ref "R5") (pin "2") (pinfunction "2_2") (pintype "passive"))
      (node (ref "U3") (pin "24") (pinfunction "MOSI_24") (pintype "input"))
    )
    (net (code "39") (name "Net-(U3-REGOUT)") (class "Default")
      (node (ref "C14") (pin "1") (pinfunction "1_1") (pintype "passive"))
      (node (ref "U3") (pin "10") (pinfunction "REGOUT_10") (pintype "power_in"))
    )
    (net (code "40") (name "Net-(U3-SCK)") (class "Default")
      (node (ref "R3") (pin "2") (pinfunction "2_2") (pintype "passive"))
      (node (ref "U3") (pin "23") (pinfunction "SCK_23") (pintype "input"))
    )
    (net (code "41") (name "Net-(U3-VDD)") (class "Default")
      (node (ref "C7") (pin "1") (pinfunction "1_1") (pintype "passive"))
      (node (ref "L3") (pin "1") (pinfunction "1_1") (pintype "passive"))
      (node (ref "U3") (pin "13") (pinfunction "VDD_13") (pintype "power_in"))
    )
    (net (code "42") (name "Net-(U4-C1)") (class "Default")
      (node (ref "C22") (pin "1") (pinfunction "1_1") (pintype "passive"))
      (node (ref "U4") (pin "10") (pinfunction "C1_10") (pintype "passive"))
    )
    (net (code "43") (name "Net-(U4-MISO)") (class "Default")
      (node (ref "R8") (pin "2") (pinfunction "2_2") (pintype "passive"))
      (node (ref "U4") (pin "5") (pinfunction "MISO_5") (pintype "output"))
    )
    (net (code "44") (name "Net-(U4-MOSI)") (class "Default")
      (node (ref "R9") (pin "2") (pinfunction "2_2") (pintype "passive"))
      (node (ref "U4") (pin "16") (pinfunction "MOSI_16") (pintype "input"))
    )
    (net (code "45") (name "Net-(U4-SCK)") (class "Default")
      (node (ref "R7") (pin "2") (pinfunction "2_2") (pintype "passive"))
      (node (ref "U4") (pin "1") (pinfunction "SCK_1") (pintype "input"))
    )
    (net (code "46") (name "Net-(U4-SETC)") (class "Default")
      (node (ref "C17") (pin "2") (pinfunction "2_2") (pintype "passive"))
      (node (ref "U4") (pin "12") (pinfunction "SETC_12") (pintype "passive"))
    )
    (net (code "47") (name "Net-(U4-SETP)") (class "Default")
      (node (ref "C17") (pin "1") (pinfunction "1_1") (pintype "passive"))
      (node (ref "U4") (pin "8") (pinfunction "SETP_8") (pintype "passive"))
    )
    (net (code "48") (name "Net-(U4-VDD)") (class "Default")
      (node (ref "C23") (pin "1") (pinfunction "1_1") (pintype "passive"))
      (node (ref "U4") (pin "13") (pinfunction "VDDIO_13") (pintype "power_in"))
      (node (ref "U4") (pin "2") (pinfunction "VDD_2") (pintype "power_in"))
    )
    (net (code "49") (name "USB_GND") (class "Default")
      (node (ref "C1") (pin "2") (pinfunction "2_2") (pintype "passive"))
      (node (ref "J1") (pin "2") (pintype "passive"))
      (node (ref "J2") (pin "5") (pinfunction "GND_5") (pintype "power_in"))
      (node (ref "L2") (pin "1") (pinfunction "1_1") (pintype "passive"))
    )
    (net (code "50") (name "VCC") (class "Default")
      (node (ref "C1") (pin "1") (pinfunction "1_1") (pintype "passive"))
      (node (ref "J1") (pin "1") (pintype "passive"))
      (node (ref "J2") (pin "1") (pinfunction "PWR_1") (pintype "power_in"))
      (node (ref "L1") (pin "1") (pinfunction "1_1") (pintype "passive"))
      (node (ref "TP1") (pin "1") (pinfunction "1_1") (pintype "passive"))
    )
    (net (code "51") (name "VUSB") (class "Default")
      (node (ref "C2") (pin "1") (pinfunction "1_1") (pintype "passive"))
      (node (ref "C3") (pin "1") (pinfunction "1_1") (pintype "passive"))
      (node (ref "L1") (pin "2") (pinfunction "2_2") (pintype "passive"))
      (node (ref "U2") (pin "4") (pinfunction "VEN_4") (pintype "input"))
      (node (ref "U2") (pin "6") (pinfunction "VIN_6") (pintype "power_in"))
    )
    (net (code "52") (name "unconnected-(J2-ID-Pad4)") (class "Default")
      (node (ref "J2") (pin "4") (pinfunction "ID_4") (pintype "passive+no_connect"))
    )
    (net (code "53") (name "unconnected-(J3-Pad8)") (class "Default")
      (node (ref "J3") (pin "8") (pintype "passive"))
    )
    (net (code "54") (name "unconnected-(U1-PA3-Pad13)") (class "Default")
      (node (ref "U1") (pin "13") (pinfunction "PA3_13") (pintype "bidirectional+no_connect"))
    )
    (net (code "55") (name "unconnected-(U1-PA15-Pad38)") (class "Default")
      (node (ref "U1") (pin "38") (pinfunction "PA15_38") (pintype "bidirectional+no_connect"))
    )
    (net (code "56") (name "unconnected-(U1-PB6-Pad42)") (class "Default")
      (node (ref "U1") (pin "42") (pinfunction "PB6_42") (pintype "bidirectional+no_connect"))
    )
    (net (code "57") (name "unconnected-(U1-PB7-Pad43)") (class "Default")
      (node (ref "U1") (pin "43") (pinfunction "PB7_43") (pintype "bidirectional+no_connect"))
    )
    (net (code "58") (name "unconnected-(U1-PB8-Pad45)") (class "Default")
      (node (ref "U1") (pin "45") (pinfunction "PB8_45") (pintype "bidirectional+no_connect"))
    )
    (net (code "59") (name "unconnected-(U1-PC13{slash}TAMPER-RTC-Pad2)") (class "Default")
      (node (ref "U1") (pin "2") (pinfunction "PC13/TAMPER-RTC_2") (pintype "bidirectional+no_connect"))
    )
    (net (code "60") (name "unconnected-(U1-PC14{slash}OSC32_IN-Pad3)") (class "Default")
      (node (ref "U1") (pin "3") (pinfunction "PC14/OSC32_IN_3") (pintype "input+no_connect"))
    )
    (net (code "61") (name "unconnected-(U1-PC15{slash}OSC32_OUT-Pad4)") (class "Default")
      (node (ref "U1") (pin "4") (pinfunction "PC15/OSC32_OUT_4") (pintype "output+no_connect"))
    )
    (net (code "62") (name "unconnected-(U3-AUX_CL-Pad7)") (class "Default")
      (node (ref "U3") (pin "7") (pinfunction "AUX_CL_7") (pintype "input+no_connect"))
    )
    (net (code "63") (name "unconnected-(U3-AUX_DA-Pad6)") (class "Default")
      (node (ref "U3") (pin "6") (pinfunction "AUX_DA_6") (pintype "bidirectional+no_connect"))
    )
    (net (code "64") (name "unconnected-(U3-CLKOUT-Pad22)") (class "Default")
      (node (ref "U3") (pin "22") (pinfunction "CLKOUT_22") (pintype "output+no_connect"))
    )
    (net (code "65") (name "unconnected-(U3-NC-Pad2)") (class "Default")
      (node (ref "U3") (pin "2") (pinfunction "NC_2") (pintype "passive+no_connect"))
    )
    (net (code "66") (name "unconnected-(U3-NC-Pad3)") (class "Default")
      (node (ref "U3") (pin "3") (pinfunction "NC_3") (pintype "passive+no_connect"))
    )
    (net (code "67") (name "unconnected-(U3-NC-Pad4)") (class "Default")
      (node (ref "U3") (pin "4") (pinfunction "NC_4") (pintype "passive+no_connect"))
    )
    (net (code "68") (name "unconnected-(U3-NC-Pad5)") (class "Default")
      (node (ref "U3") (pin "5") (pinfunction "NC_5") (pintype "passive+no_connect"))
    )
    (net (code "69") (name "unconnected-(U3-NC-Pad14)") (class "Default")
      (node (ref "U3") (pin "14") (pinfunction "NC_14") (pintype "passive+no_connect"))
    )
    (net (code "70") (name "unconnected-(U3-NC-Pad15)") (class "Default")
      (node (ref "U3") (pin "15") (pinfunction "NC_15") (pintype "passive+no_connect"))
    )
    (net (code "71") (name "unconnected-(U3-NC-Pad16)") (class "Default")
      (node (ref "U3") (pin "16") (pinfunction "NC_16") (pintype "passive+no_connect"))
    )
    (net (code "72") (name "unconnected-(U3-NC-Pad17)") (class "Default")
      (node (ref "U3") (pin "17") (pinfunction "NC_17") (pintype "passive+no_connect"))
    )
    (net (code "73") (name "unconnected-(U3-RESV-Pad19)") (class "Default")
      (node (ref "U3") (pin "19") (pinfunction "RESV_19") (pintype "passive+no_connect"))
    )
    (net (code "74") (name "unconnected-(U3-RESV-Pad21)") (class "Default")
      (node (ref "U3") (pin "21") (pinfunction "RESV_21") (pintype "passive+no_connect"))
    )
    (net (code "75") (name "unconnected-(U4-NC-Pad3)") (class "Default")
      (node (ref "U4") (pin "3") (pinfunction "NC_3") (pintype "passive+no_connect"))
    )
    (net (code "76") (name "unconnected-(U4-NC-Pad7)") (class "Default")
      (node (ref "U4") (pin "7") (pinfunction "NC_7") (pintype "passive+no_connect"))
    )
    (net (code "77") (name "unconnected-(U4-NC-Pad14)") (class "Default")
      (node (ref "U4") (pin "14") (pinfunction "NC_14") (pintype "passive+no_connect"))
    )
  )
)
